# MB_RELAY.net
KiCad netlist of a schematic drawn in Altium Designer
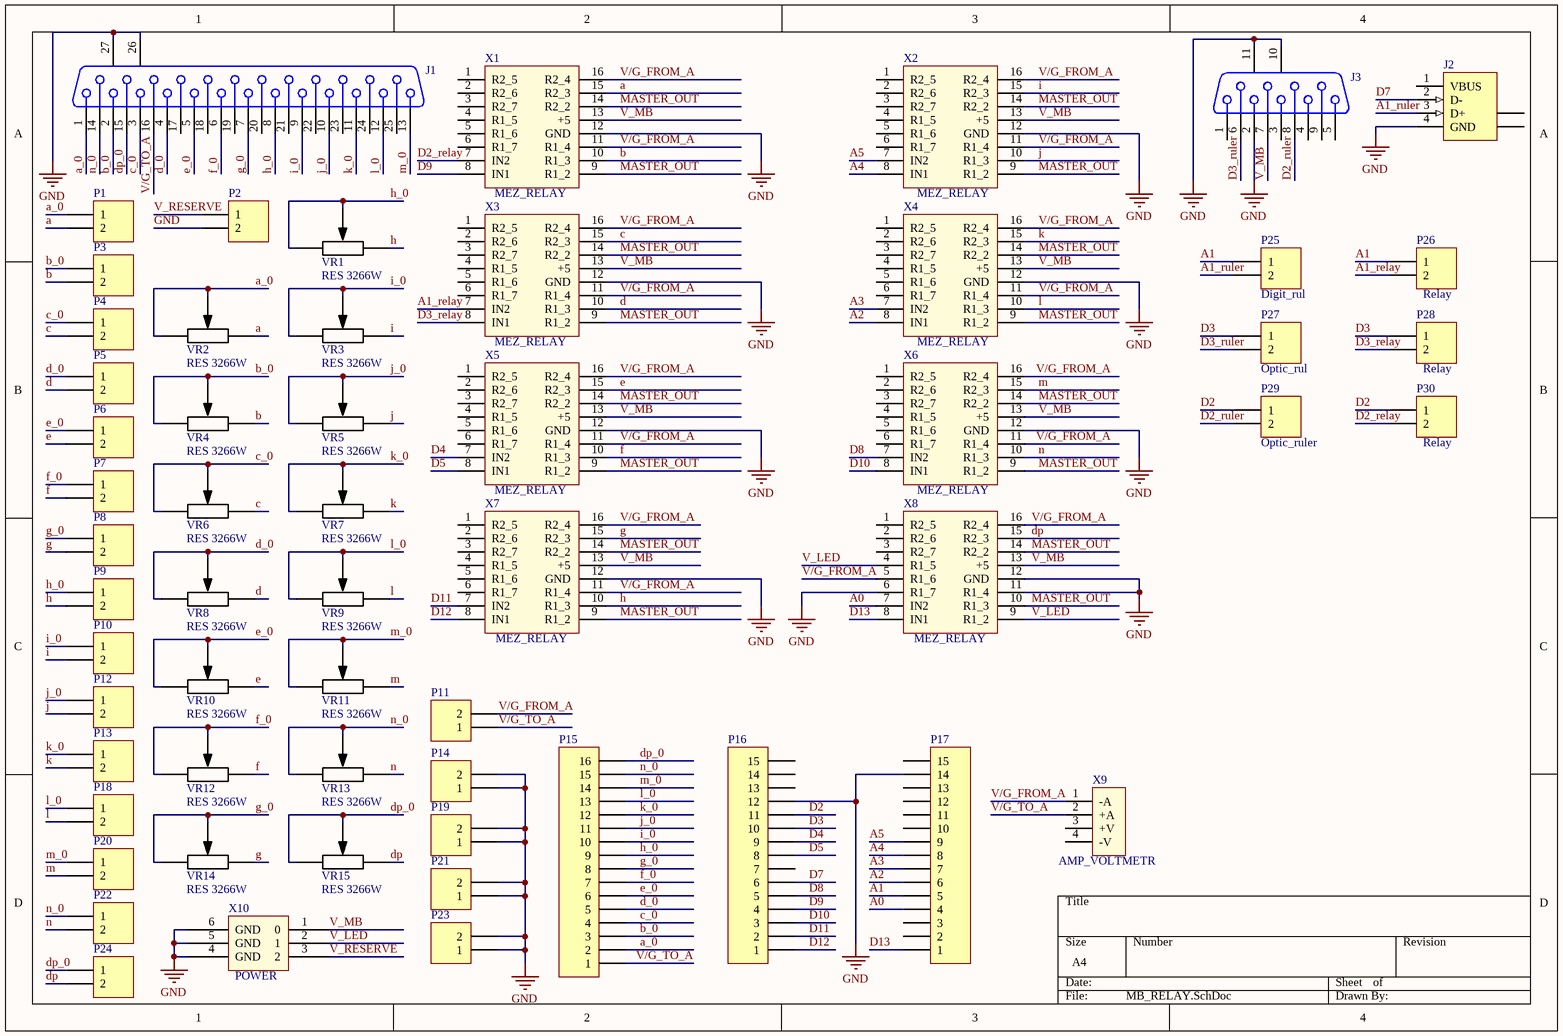
[diagram p0: MB_RELAY.SchDoc]

(export (version "E")
  (design (tool "Eeschema 10.0.6"))
  (components
    (comp (ref "J1")
      (value "D Connector 25")
      (footprint "DSUB1.385-2H25A")
      (description "Receptacle Assembly, 25 Position, Right Angle")
      (fields (field (name "PUBLISHER") "Altium Limited"))
      (libsource (lib "Miscellaneous Connectors") (part "D Connector 25"))
    )
    (comp (ref "J2")
      (value "1-353576-1")
      (footprint "353576")
      (description "USB 1.1, Right Angle, SMT, A Type, Receptacle, 4 Position, White")
      (fields (field (name "PUBLISHER") "Altium Limited"))
      (libsource (lib "AMP Serial Bus USB") (part "1-353576-1"))
    )
    (comp (ref "J3")
      (value "D Connector 9")
      (footprint "DSUB1.385-2H9")
      (description "Receptacle Assembly, 9 Position, Right Angle")
      (fields (field (name "PUBLISHER") "Altium Limited"))
      (libsource (lib "Miscellaneous Connectors") (part "D Connector 9"))
    )
    (comp (ref "P1")
      (value "Header 2")
      (footprint "HDR1X2")
      (description "Header, 2-Pin")
      (fields (field (name "PUBLISHER") "Altium Limited"))
      (libsource (lib "Miscellaneous Connectors") (part "Header 2"))
    )
    (comp (ref "P2")
      (value "Header 2")
      (footprint "HDR1X2")
      (description "Header, 2-Pin")
      (fields (field (name "PUBLISHER") "Altium Limited"))
      (libsource (lib "Miscellaneous Connectors") (part "Header 2"))
    )
    (comp (ref "P3")
      (value "Header 2")
      (footprint "HDR1X2")
      (description "Header, 2-Pin")
      (fields (field (name "PUBLISHER") "Altium Limited"))
      (libsource (lib "Miscellaneous Connectors") (part "Header 2"))
    )
    (comp (ref "P4")
      (value "Header 2")
      (footprint "HDR1X2")
      (description "Header, 2-Pin")
      (fields (field (name "PUBLISHER") "Altium Limited"))
      (libsource (lib "Miscellaneous Connectors") (part "Header 2"))
    )
    (comp (ref "P5")
      (value "Header 2")
      (footprint "HDR1X2")
      (description "Header, 2-Pin")
      (fields (field (name "PUBLISHER") "Altium Limited"))
      (libsource (lib "Miscellaneous Connectors") (part "Header 2"))
    )
    (comp (ref "P6")
      (value "GND")
      (footprint "HDR1X2")
      (description "Header, 2-Pin")
      (fields (field (name "PUBLISHER") "Altium Limited"))
      (libsource (lib "Miscellaneous Connectors") (part "Header 2"))
    )
    (comp (ref "P7")
      (value "GND")
      (footprint "HDR1X2")
      (description "Header, 2-Pin")
      (fields (field (name "PUBLISHER") "Altium Limited"))
      (libsource (lib "Miscellaneous Connectors") (part "Header 2"))
    )
    (comp (ref "P8")
      (value "GND")
      (footprint "HDR1X2")
      (description "Header, 2-Pin")
      (fields (field (name "PUBLISHER") "Altium Limited"))
      (libsource (lib "Miscellaneous Connectors") (part "Header 2"))
    )
    (comp (ref "P9")
      (value "GND")
      (footprint "HDR1X2")
      (description "Header, 2-Pin")
      (fields (field (name "PUBLISHER") "Altium Limited"))
      (libsource (lib "Miscellaneous Connectors") (part "Header 2"))
    )
    (comp (ref "P10")
      (value "Header 2")
      (footprint "HDR1X2")
      (description "Header, 2-Pin")
      (fields (field (name "PUBLISHER") "Altium Limited"))
      (libsource (lib "Miscellaneous Connectors") (part "Header 2"))
    )
    (comp (ref "P11")
      (value "Header 2")
      (footprint "HDR1X2")
      (description "Header, 2-Pin")
      (fields (field (name "PUBLISHER") "Altium Limited"))
      (libsource (lib "") (part "Header 2_1"))
    )
    (comp (ref "P12")
      (value "Header 2")
      (footprint "HDR1X2")
      (description "Header, 2-Pin")
      (fields (field (name "PUBLISHER") "Altium Limited"))
      (libsource (lib "Miscellaneous Connectors") (part "Header 2"))
    )
    (comp (ref "P13")
      (value "GND")
      (footprint "HDR1X2")
      (description "Header, 2-Pin")
      (fields (field (name "PUBLISHER") "Altium Limited"))
      (libsource (lib "Miscellaneous Connectors") (part "Header 2"))
    )
    (comp (ref "P14")
      (value "GND")
      (footprint "HDR1X2")
      (description "Header, 2-Pin")
      (fields (field (name "PUBLISHER") "Altium Limited"))
      (libsource (lib "") (part "Header 2_1"))
    )
    (comp (ref "P15")
      (value "Header 16")
      (footprint "HDR1X16")
      (description "Header, 16-Pin")
      (fields (field (name "PUBLISHER") "Altium Limited"))
      (libsource (lib "Miscellaneous Connectors") (part "Header 16"))
    )
    (comp (ref "P16")
      (value "Header 15")
      (footprint "HDR1X15")
      (description "Header, 15-Pin")
      (fields (field (name "PUBLISHER") "Altium Limited"))
      (libsource (lib "Miscellaneous Connectors") (part "Header 15"))
    )
    (comp (ref "P17")
      (value "Header 15")
      (footprint "HDR1X15")
      (description "Header, 15-Pin")
      (fields (field (name "PUBLISHER") "Altium Limited"))
      (libsource (lib "") (part "Header 15_1"))
    )
    (comp (ref "P18")
      (value "GND")
      (footprint "HDR1X2")
      (description "Header, 2-Pin")
      (fields (field (name "PUBLISHER") "Altium Limited"))
      (libsource (lib "Miscellaneous Connectors") (part "Header 2"))
    )
    (comp (ref "P19")
      (value "GND")
      (footprint "HDR1X2")
      (description "Header, 2-Pin")
      (fields (field (name "PUBLISHER") "Altium Limited"))
      (libsource (lib "") (part "Header 2_1"))
    )
    (comp (ref "P20")
      (value "GND")
      (footprint "HDR1X2")
      (description "Header, 2-Pin")
      (fields (field (name "PUBLISHER") "Altium Limited"))
      (libsource (lib "Miscellaneous Connectors") (part "Header 2"))
    )
    (comp (ref "P21")
      (value "GND")
      (footprint "HDR1X2")
      (description "Header, 2-Pin")
      (fields (field (name "PUBLISHER") "Altium Limited"))
      (libsource (lib "") (part "Header 2_1"))
    )
    (comp (ref "P22")
      (value "GND")
      (footprint "HDR1X2")
      (description "Header, 2-Pin")
      (fields (field (name "PUBLISHER") "Altium Limited"))
      (libsource (lib "Miscellaneous Connectors") (part "Header 2"))
    )
    (comp (ref "P23")
      (value "GND")
      (footprint "HDR1X2")
      (description "Header, 2-Pin")
      (fields (field (name "PUBLISHER") "Altium Limited"))
      (libsource (lib "") (part "Header 2_1"))
    )
    (comp (ref "P24")
      (value "GND")
      (footprint "HDR1X2")
      (description "Header, 2-Pin")
      (fields (field (name "PUBLISHER") "Altium Limited"))
      (libsource (lib "Miscellaneous Connectors") (part "Header 2"))
    )
    (comp (ref "P25")
      (value "Digit_rul")
      (footprint "HDR1X2")
      (description "Header, 2-Pin")
      (fields (field (name "PUBLISHER") "Altium Limited"))
      (libsource (lib "Miscellaneous Connectors") (part "Header 2"))
    )
    (comp (ref "P26")
      (value "Relay")
      (footprint "HDR1X2")
      (description "Header, 2-Pin")
      (fields (field (name "PUBLISHER") "Altium Limited"))
      (libsource (lib "Miscellaneous Connectors") (part "Header 2"))
    )
    (comp (ref "P27")
      (value "Optic_rul")
      (footprint "HDR1X2")
      (description "Header, 2-Pin")
      (fields (field (name "PUBLISHER") "Altium Limited"))
      (libsource (lib "Miscellaneous Connectors") (part "Header 2"))
    )
    (comp (ref "P28")
      (value "Relay")
      (footprint "HDR1X2")
      (description "Header, 2-Pin")
      (fields (field (name "PUBLISHER") "Altium Limited"))
      (libsource (lib "Miscellaneous Connectors") (part "Header 2"))
    )
    (comp (ref "P29")
      (value "Optic_ruler")
      (footprint "HDR1X2")
      (description "Header, 2-Pin")
      (fields (field (name "PUBLISHER") "Altium Limited"))
      (libsource (lib "Miscellaneous Connectors") (part "Header 2"))
    )
    (comp (ref "P30")
      (value "Relay")
      (footprint "HDR1X2")
      (description "Header, 2-Pin")
      (fields (field (name "PUBLISHER") "Altium Limited"))
      (libsource (lib "Miscellaneous Connectors") (part "Header 2"))
    )
    (comp (ref "VR1")
      (value "RES 3266W")
      (footprint "aab_Passive:RES 3266W")
      (libsource (lib "aab_Schlib") (part "RES 3266W"))
    )
    (comp (ref "VR2")
      (value "RES 3266W")
      (footprint "aab_Passive:RES 3266W")
      (libsource (lib "aab_Schlib") (part "RES 3266W"))
    )
    (comp (ref "VR3")
      (value "RES 3266W")
      (footprint "aab_Passive:RES 3266W")
      (libsource (lib "aab_Schlib") (part "RES 3266W"))
    )
    (comp (ref "VR4")
      (value "RES 3266W")
      (footprint "aab_Passive:RES 3266W")
      (libsource (lib "aab_Schlib") (part "RES 3266W"))
    )
    (comp (ref "VR5")
      (value "RES 3266W")
      (footprint "aab_Passive:RES 3266W")
      (libsource (lib "aab_Schlib") (part "RES 3266W"))
    )
    (comp (ref "VR6")
      (value "RES 3266W")
      (footprint "aab_Passive:RES 3266W")
      (libsource (lib "aab_Schlib") (part "RES 3266W"))
    )
    (comp (ref "VR7")
      (value "RES 3266W")
      (footprint "aab_Passive:RES 3266W")
      (libsource (lib "aab_Schlib") (part "RES 3266W"))
    )
    (comp (ref "VR8")
      (value "RES 3266W")
      (footprint "aab_Passive:RES 3266W")
      (libsource (lib "aab_Schlib") (part "RES 3266W"))
    )
    (comp (ref "VR9")
      (value "RES 3266W")
      (footprint "aab_Passive:RES 3266W")
      (libsource (lib "aab_Schlib") (part "RES 3266W"))
    )
    (comp (ref "VR10")
      (value "RES 3266W")
      (footprint "aab_Passive:RES 3266W")
      (libsource (lib "aab_Schlib") (part "RES 3266W"))
    )
    (comp (ref "VR11")
      (value "RES 3266W")
      (footprint "aab_Passive:RES 3266W")
      (libsource (lib "aab_Schlib") (part "RES 3266W"))
    )
    (comp (ref "VR12")
      (value "RES 3266W")
      (footprint "aab_Passive:RES 3266W")
      (libsource (lib "aab_Schlib") (part "RES 3266W"))
    )
    (comp (ref "VR13")
      (value "RES 3266W")
      (footprint "aab_Passive:RES 3266W")
      (libsource (lib "aab_Schlib") (part "RES 3266W"))
    )
    (comp (ref "VR14")
      (value "RES 3266W")
      (footprint "aab_Passive:RES 3266W")
      (libsource (lib "aab_Schlib") (part "RES 3266W"))
    )
    (comp (ref "VR15")
      (value "RES 3266W")
      (footprint "aab_Passive:RES 3266W")
      (libsource (lib "aab_Schlib") (part "RES 3266W"))
    )
    (comp (ref "X1")
      (value "MEZ_RELAY")
      (footprint "MEZ_RELAY")
      (libsource (lib "msp_SchLib") (part "MEZ_RELAY"))
    )
    (comp (ref "X2")
      (value "MEZ_RELAY")
      (footprint "MEZ_RELAY")
      (libsource (lib "msp_SchLib") (part "MEZ_RELAY"))
    )
    (comp (ref "X3")
      (value "MEZ_RELAY")
      (footprint "MEZ_RELAY")
      (libsource (lib "msp_SchLib") (part "MEZ_RELAY"))
    )
    (comp (ref "X4")
      (value "MEZ_RELAY")
      (footprint "MEZ_RELAY")
      (libsource (lib "msp_SchLib") (part "MEZ_RELAY"))
    )
    (comp (ref "X5")
      (value "MEZ_RELAY")
      (footprint "MEZ_RELAY")
      (libsource (lib "msp_SchLib") (part "MEZ_RELAY"))
    )
    (comp (ref "X6")
      (value "MEZ_RELAY")
      (footprint "MEZ_RELAY")
      (libsource (lib "msp_SchLib") (part "MEZ_RELAY"))
    )
    (comp (ref "X7")
      (value "MEZ_RELAY")
      (footprint "MEZ_RELAY")
      (libsource (lib "msp_SchLib") (part "MEZ_RELAY"))
    )
    (comp (ref "X8")
      (value "MEZ_RELAY")
      (footprint "MEZ_RELAY")
      (libsource (lib "msp_SchLib") (part "MEZ_RELAY"))
    )
    (comp (ref "X9")
      (value "AMP_VOLTMETR")
      (footprint "vpl_Passive:AMP_VOLTMETER")
      (libsource (lib "msp_SchLib") (part "AMP_VOLTMETR"))
    )
    (comp (ref "X10")
      (value "POWER")
      (footprint "vpl_Passive:POWER")
      (libsource (lib "msp_SchLib") (part "POWER"))
    )
  )
  (nets
    (net (code "1") (name "/A0") (class "Default")
      (node (ref "P17") (pin "4") (pinfunction "4_4") (pintype "passive"))
      (node (ref "X8") (pin "7") (pinfunction "IN2_7") (pintype "passive"))
    )
    (net (code "2") (name "/A1") (class "Default")
      (node (ref "P17") (pin "5") (pinfunction "5_5") (pintype "passive"))
      (node (ref "P25") (pin "1") (pinfunction "1_1") (pintype "passive"))
      (node (ref "P26") (pin "1") (pinfunction "1_1") (pintype "passive"))
    )
    (net (code "3") (name "/A1_relay") (class "Default")
      (node (ref "P26") (pin "2") (pinfunction "2_2") (pintype "passive"))
      (node (ref "X3") (pin "7") (pinfunction "IN2_7") (pintype "passive"))
    )
    (net (code "4") (name "/A1_ruler") (class "Default")
      (node (ref "J2") (pin "3") (pinfunction "D+_3") (pintype "input"))
      (node (ref "P25") (pin "2") (pinfunction "2_2") (pintype "passive"))
    )
    (net (code "5") (name "/A2") (class "Default")
      (node (ref "P17") (pin "6") (pinfunction "6_6") (pintype "passive"))
      (node (ref "X4") (pin "8") (pinfunction "IN1_8") (pintype "passive"))
    )
    (net (code "6") (name "/A3") (class "Default")
      (node (ref "P17") (pin "7") (pinfunction "7_7") (pintype "passive"))
      (node (ref "X4") (pin "7") (pinfunction "IN2_7") (pintype "passive"))
    )
    (net (code "7") (name "/A4") (class "Default")
      (node (ref "P17") (pin "8") (pinfunction "8_8") (pintype "passive"))
      (node (ref "X2") (pin "8") (pinfunction "IN1_8") (pintype "passive"))
    )
    (net (code "8") (name "/A5") (class "Default")
      (node (ref "P17") (pin "9") (pinfunction "9_9") (pintype "passive"))
      (node (ref "X2") (pin "7") (pinfunction "IN2_7") (pintype "passive"))
    )
    (net (code "9") (name "/D2") (class "Default")
      (node (ref "P16") (pin "11") (pinfunction "11_11") (pintype "passive"))
      (node (ref "P29") (pin "1") (pinfunction "1_1") (pintype "passive"))
      (node (ref "P30") (pin "1") (pinfunction "1_1") (pintype "passive"))
    )
    (net (code "10") (name "/D2_relay") (class "Default")
      (node (ref "P30") (pin "2") (pinfunction "2_2") (pintype "passive"))
      (node (ref "X1") (pin "7") (pinfunction "IN2_7") (pintype "passive"))
    )
    (net (code "11") (name "/D2_ruler") (class "Default")
      (node (ref "J3") (pin "8") (pinfunction "8_8") (pintype "passive"))
      (node (ref "P29") (pin "2") (pinfunction "2_2") (pintype "passive"))
    )
    (net (code "12") (name "/D3") (class "Default")
      (node (ref "P16") (pin "10") (pinfunction "10_10") (pintype "passive"))
      (node (ref "P27") (pin "1") (pinfunction "1_1") (pintype "passive"))
      (node (ref "P28") (pin "1") (pinfunction "1_1") (pintype "passive"))
    )
    (net (code "13") (name "/D3_relay") (class "Default")
      (node (ref "P28") (pin "2") (pinfunction "2_2") (pintype "passive"))
      (node (ref "X3") (pin "8") (pinfunction "IN1_8") (pintype "passive"))
    )
    (net (code "14") (name "/D3_ruler") (class "Default")
      (node (ref "J3") (pin "6") (pinfunction "6_6") (pintype "passive"))
      (node (ref "P27") (pin "2") (pinfunction "2_2") (pintype "passive"))
    )
    (net (code "15") (name "/D4") (class "Default")
      (node (ref "P16") (pin "9") (pinfunction "9_9") (pintype "passive"))
      (node (ref "X5") (pin "7") (pinfunction "IN2_7") (pintype "passive"))
    )
    (net (code "16") (name "/D5") (class "Default")
      (node (ref "P16") (pin "8") (pinfunction "8_8") (pintype "passive"))
      (node (ref "X5") (pin "8") (pinfunction "IN1_8") (pintype "passive"))
    )
    (net (code "17") (name "/D7") (class "Default")
      (node (ref "J2") (pin "2") (pinfunction "D-_2") (pintype "input"))
      (node (ref "P16") (pin "6") (pinfunction "6_6") (pintype "passive"))
    )
    (net (code "18") (name "/D8") (class "Default")
      (node (ref "P16") (pin "5") (pinfunction "5_5") (pintype "passive"))
      (node (ref "X6") (pin "7") (pinfunction "IN2_7") (pintype "passive"))
    )
    (net (code "19") (name "/D9") (class "Default")
      (node (ref "P16") (pin "4") (pinfunction "4_4") (pintype "passive"))
      (node (ref "X1") (pin "8") (pinfunction "IN1_8") (pintype "passive"))
    )
    (net (code "20") (name "/D10") (class "Default")
      (node (ref "P16") (pin "3") (pinfunction "3_3") (pintype "passive"))
      (node (ref "X6") (pin "8") (pinfunction "IN1_8") (pintype "passive"))
    )
    (net (code "21") (name "/D11") (class "Default")
      (node (ref "P16") (pin "2") (pinfunction "2_2") (pintype "passive"))
      (node (ref "X7") (pin "7") (pinfunction "IN2_7") (pintype "passive"))
    )
    (net (code "22") (name "/D12") (class "Default")
      (node (ref "P16") (pin "1") (pinfunction "1_1") (pintype "passive"))
      (node (ref "X7") (pin "8") (pinfunction "IN1_8") (pintype "passive"))
    )
    (net (code "23") (name "/D13") (class "Default")
      (node (ref "P17") (pin "1") (pinfunction "1_1") (pintype "passive"))
      (node (ref "X8") (pin "8") (pinfunction "IN1_8") (pintype "passive"))
    )
    (net (code "24") (name "/MASTER_OUT") (class "Default")
      (node (ref "X1") (pin "14") (pinfunction "R2_2_14") (pintype "passive"))
      (node (ref "X1") (pin "9") (pinfunction "R1_2_9") (pintype "passive"))
      (node (ref "X2") (pin "14") (pinfunction "R2_2_14") (pintype "passive"))
      (node (ref "X2") (pin "9") (pinfunction "R1_2_9") (pintype "passive"))
      (node (ref "X3") (pin "14") (pinfunction "R2_2_14") (pintype "passive"))
      (node (ref "X3") (pin "9") (pinfunction "R1_2_9") (pintype "passive"))
      (node (ref "X4") (pin "14") (pinfunction "R2_2_14") (pintype "passive"))
      (node (ref "X4") (pin "9") (pinfunction "R1_2_9") (pintype "passive"))
      (node (ref "X5") (pin "14") (pinfunction "R2_2_14") (pintype "passive"))
      (node (ref "X5") (pin "9") (pinfunction "R1_2_9") (pintype "passive"))
      (node (ref "X6") (pin "14") (pinfunction "R2_2_14") (pintype "passive"))
      (node (ref "X6") (pin "9") (pinfunction "R1_2_9") (pintype "passive"))
      (node (ref "X7") (pin "14") (pinfunction "R2_2_14") (pintype "passive"))
      (node (ref "X7") (pin "9") (pinfunction "R1_2_9") (pintype "passive"))
      (node (ref "X8") (pin "10") (pinfunction "R1_3_10") (pintype "passive"))
      (node (ref "X8") (pin "14") (pinfunction "R2_2_14") (pintype "passive"))
    )
    (net (code "25") (name "/V_LED") (class "Default")
      (node (ref "X10") (pin "2") (pinfunction "1_2") (pintype "passive"))
      (node (ref "X8") (pin "4") (pinfunction "R1_5_4") (pintype "passive"))
      (node (ref "X8") (pin "9") (pinfunction "R1_2_9") (pintype "passive"))
    )
    (net (code "26") (name "/V_MB") (class "Default")
      (node (ref "J3") (pin "7") (pinfunction "7_7") (pintype "passive"))
      (node (ref "X1") (pin "13") (pinfunction "+5_13") (pintype "passive"))
      (node (ref "X10") (pin "1") (pinfunction "0_1") (pintype "passive"))
      (node (ref "X2") (pin "13") (pinfunction "+5_13") (pintype "passive"))
      (node (ref "X3") (pin "13") (pinfunction "+5_13") (pintype "passive"))
      (node (ref "X4") (pin "13") (pinfunction "+5_13") (pintype "passive"))
      (node (ref "X5") (pin "13") (pinfunction "+5_13") (pintype "passive"))
      (node (ref "X6") (pin "13") (pinfunction "+5_13") (pintype "passive"))
      (node (ref "X7") (pin "13") (pinfunction "+5_13") (pintype "passive"))
      (node (ref "X8") (pin "13") (pinfunction "+5_13") (pintype "passive"))
    )
    (net (code "27") (name "/V_RESERVE") (class "Default")
      (node (ref "P2") (pin "1") (pinfunction "1_1") (pintype "passive"))
      (node (ref "X10") (pin "3") (pinfunction "2_3") (pintype "passive"))
    )
    (net (code "28") (name "/V{slash}G_FROM_A") (class "Default")
      (node (ref "P11") (pin "2") (pinfunction "2_2") (pintype "passive"))
      (node (ref "X1") (pin "11") (pinfunction "R1_4_11") (pintype "passive"))
      (node (ref "X1") (pin "16") (pinfunction "R2_4_16") (pintype "passive"))
      (node (ref "X2") (pin "11") (pinfunction "R1_4_11") (pintype "passive"))
      (node (ref "X2") (pin "16") (pinfunction "R2_4_16") (pintype "passive"))
      (node (ref "X3") (pin "11") (pinfunction "R1_4_11") (pintype "passive"))
      (node (ref "X3") (pin "16") (pinfunction "R2_4_16") (pintype "passive"))
      (node (ref "X4") (pin "11") (pinfunction "R1_4_11") (pintype "passive"))
      (node (ref "X4") (pin "16") (pinfunction "R2_4_16") (pintype "passive"))
      (node (ref "X5") (pin "11") (pinfunction "R1_4_11") (pintype "passive"))
      (node (ref "X5") (pin "16") (pinfunction "R2_4_16") (pintype "passive"))
      (node (ref "X6") (pin "11") (pinfunction "R1_4_11") (pintype "passive"))
      (node (ref "X6") (pin "16") (pinfunction "R2_4_16") (pintype "passive"))
      (node (ref "X7") (pin "11") (pinfunction "R1_4_11") (pintype "passive"))
      (node (ref "X7") (pin "16") (pinfunction "R2_4_16") (pintype "passive"))
      (node (ref "X8") (pin "16") (pinfunction "R2_4_16") (pintype "passive"))
      (node (ref "X8") (pin "5") (pinfunction "R1_6_5") (pintype "passive"))
      (node (ref "X9") (pin "1") (pinfunction "-A_1") (pintype "passive"))
    )
    (net (code "29") (name "/V{slash}G_TO_A") (class "Default")
      (node (ref "J1") (pin "16") (pinfunction "16_16") (pintype "passive"))
      (node (ref "P11") (pin "1") (pinfunction "1_1") (pintype "passive"))
      (node (ref "P15") (pin "1") (pinfunction "1_1") (pintype "passive"))
      (node (ref "X9") (pin "2") (pinfunction "+A_2") (pintype "passive"))
    )
    (net (code "30") (name "/a") (class "Default")
      (node (ref "P1") (pin "2") (pinfunction "2_2") (pintype "passive"))
      (node (ref "VR2") (pin "3") (pinfunction "3_3") (pintype "passive"))
      (node (ref "X1") (pin "15") (pinfunction "R2_3_15") (pintype "passive"))
    )
    (net (code "31") (name "/a_0") (class "Default")
      (node (ref "J1") (pin "1") (pinfunction "1_1") (pintype "passive"))
      (node (ref "P1") (pin "1") (pinfunction "1_1") (pintype "passive"))
      (node (ref "P15") (pin "2") (pinfunction "2_2") (pintype "passive"))
      (node (ref "VR2") (pin "1") (pinfunction "1_1") (pintype "passive"))
      (node (ref "VR2") (pin "2") (pinfunction "2_2") (pintype "passive"))
    )
    (net (code "32") (name "/b") (class "Default")
      (node (ref "P3") (pin "2") (pinfunction "2_2") (pintype "passive"))
      (node (ref "VR4") (pin "3") (pinfunction "3_3") (pintype "passive"))
      (node (ref "X1") (pin "10") (pinfunction "R1_3_10") (pintype "passive"))
    )
    (net (code "33") (name "/b_0") (class "Default")
      (node (ref "J1") (pin "2") (pinfunction "2_2") (pintype "passive"))
      (node (ref "P15") (pin "3") (pinfunction "3_3") (pintype "passive"))
      (node (ref "P3") (pin "1") (pinfunction "1_1") (pintype "passive"))
      (node (ref "VR4") (pin "1") (pinfunction "1_1") (pintype "passive"))
      (node (ref "VR4") (pin "2") (pinfunction "2_2") (pintype "passive"))
    )
    (net (code "34") (name "/c") (class "Default")
      (node (ref "P4") (pin "2") (pinfunction "2_2") (pintype "passive"))
      (node (ref "VR6") (pin "3") (pinfunction "3_3") (pintype "passive"))
      (node (ref "X3") (pin "15") (pinfunction "R2_3_15") (pintype "passive"))
    )
    (net (code "35") (name "/c_0") (class "Default")
      (node (ref "J1") (pin "3") (pinfunction "3_3") (pintype "passive"))
      (node (ref "P15") (pin "4") (pinfunction "4_4") (pintype "passive"))
      (node (ref "P4") (pin "1") (pinfunction "1_1") (pintype "passive"))
      (node (ref "VR6") (pin "1") (pinfunction "1_1") (pintype "passive"))
      (node (ref "VR6") (pin "2") (pinfunction "2_2") (pintype "passive"))
    )
    (net (code "36") (name "/d") (class "Default")
      (node (ref "P5") (pin "2") (pinfunction "2_2") (pintype "passive"))
      (node (ref "VR8") (pin "3") (pinfunction "3_3") (pintype "passive"))
      (node (ref "X3") (pin "10") (pinfunction "R1_3_10") (pintype "passive"))
    )
    (net (code "37") (name "/d_0") (class "Default")
      (node (ref "J1") (pin "4") (pinfunction "4_4") (pintype "passive"))
      (node (ref "P15") (pin "5") (pinfunction "5_5") (pintype "passive"))
      (node (ref "P5") (pin "1") (pinfunction "1_1") (pintype "passive"))
      (node (ref "VR8") (pin "1") (pinfunction "1_1") (pintype "passive"))
      (node (ref "VR8") (pin "2") (pinfunction "2_2") (pintype "passive"))
    )
    (net (code "38") (name "/dp") (class "Default")
      (node (ref "P24") (pin "2") (pinfunction "2_2") (pintype "passive"))
      (node (ref "VR15") (pin "3") (pinfunction "3_3") (pintype "passive"))
      (node (ref "X8") (pin "15") (pinfunction "R2_3_15") (pintype "passive"))
    )
    (net (code "39") (name "/dp_0") (class "Default")
      (node (ref "J1") (pin "15") (pinfunction "15_15") (pintype "passive"))
      (node (ref "P15") (pin "16") (pinfunction "16_16") (pintype "passive"))
      (node (ref "P24") (pin "1") (pinfunction "1_1") (pintype "passive"))
      (node (ref "VR15") (pin "1") (pinfunction "1_1") (pintype "passive"))
      (node (ref "VR15") (pin "2") (pinfunction "2_2") (pintype "passive"))
    )
    (net (code "40") (name "/e") (class "Default")
      (node (ref "P6") (pin "2") (pinfunction "2_2") (pintype "passive"))
      (node (ref "VR10") (pin "3") (pinfunction "3_3") (pintype "passive"))
      (node (ref "X5") (pin "15") (pinfunction "R2_3_15") (pintype "passive"))
    )
    (net (code "41") (name "/e_0") (class "Default")
      (node (ref "J1") (pin "5") (pinfunction "5_5") (pintype "passive"))
      (node (ref "P15") (pin "6") (pinfunction "6_6") (pintype "passive"))
      (node (ref "P6") (pin "1") (pinfunction "1_1") (pintype "passive"))
      (node (ref "VR10") (pin "1") (pinfunction "1_1") (pintype "passive"))
      (node (ref "VR10") (pin "2") (pinfunction "2_2") (pintype "passive"))
    )
    (net (code "42") (name "/f") (class "Default")
      (node (ref "P7") (pin "2") (pinfunction "2_2") (pintype "passive"))
      (node (ref "VR12") (pin "3") (pinfunction "3_3") (pintype "passive"))
      (node (ref "X5") (pin "10") (pinfunction "R1_3_10") (pintype "passive"))
    )
    (net (code "43") (name "/f_0") (class "Default")
      (node (ref "J1") (pin "6") (pinfunction "6_6") (pintype "passive"))
      (node (ref "P15") (pin "7") (pinfunction "7_7") (pintype "passive"))
      (node (ref "P7") (pin "1") (pinfunction "1_1") (pintype "passive"))
      (node (ref "VR12") (pin "1") (pinfunction "1_1") (pintype "passive"))
      (node (ref "VR12") (pin "2") (pinfunction "2_2") (pintype "passive"))
    )
    (net (code "44") (name "/g") (class "Default")
      (node (ref "P8") (pin "2") (pinfunction "2_2") (pintype "passive"))
      (node (ref "VR14") (pin "3") (pinfunction "3_3") (pintype "passive"))
      (node (ref "X7") (pin "15") (pinfunction "R2_3_15") (pintype "passive"))
    )
    (net (code "45") (name "/g_0") (class "Default")
      (node (ref "J1") (pin "7") (pinfunction "7_7") (pintype "passive"))
      (node (ref "P15") (pin "8") (pinfunction "8_8") (pintype "passive"))
      (node (ref "P8") (pin "1") (pinfunction "1_1") (pintype "passive"))
      (node (ref "VR14") (pin "1") (pinfunction "1_1") (pintype "passive"))
      (node (ref "VR14") (pin "2") (pinfunction "2_2") (pintype "passive"))
    )
    (net (code "46") (name "/h") (class "Default")
      (node (ref "P9") (pin "2") (pinfunction "2_2") (pintype "passive"))
      (node (ref "VR1") (pin "3") (pinfunction "3_3") (pintype "passive"))
      (node (ref "X7") (pin "10") (pinfunction "R1_3_10") (pintype "passive"))
    )
    (net (code "47") (name "/h_0") (class "Default")
      (node (ref "J1") (pin "8") (pinfunction "8_8") (pintype "passive"))
      (node (ref "P15") (pin "9") (pinfunction "9_9") (pintype "passive"))
      (node (ref "P9") (pin "1") (pinfunction "1_1") (pintype "passive"))
      (node (ref "VR1") (pin "1") (pinfunction "1_1") (pintype "passive"))
      (node (ref "VR1") (pin "2") (pinfunction "2_2") (pintype "passive"))
    )
    (net (code "48") (name "/i") (class "Default")
      (node (ref "P10") (pin "2") (pinfunction "2_2") (pintype "passive"))
      (node (ref "VR3") (pin "3") (pinfunction "3_3") (pintype "passive"))
      (node (ref "X2") (pin "15") (pinfunction "R2_3_15") (pintype "passive"))
    )
    (net (code "49") (name "/i_0") (class "Default")
      (node (ref "J1") (pin "9") (pinfunction "9_9") (pintype "passive"))
      (node (ref "P10") (pin "1") (pinfunction "1_1") (pintype "passive"))
      (node (ref "P15") (pin "10") (pinfunction "10_10") (pintype "passive"))
      (node (ref "VR3") (pin "1") (pinfunction "1_1") (pintype "passive"))
      (node (ref "VR3") (pin "2") (pinfunction "2_2") (pintype "passive"))
    )
    (net (code "50") (name "/j") (class "Default")
      (node (ref "P12") (pin "2") (pinfunction "2_2") (pintype "passive"))
      (node (ref "VR5") (pin "3") (pinfunction "3_3") (pintype "passive"))
      (node (ref "X2") (pin "10") (pinfunction "R1_3_10") (pintype "passive"))
    )
    (net (code "51") (name "/j_0") (class "Default")
      (node (ref "J1") (pin "10") (pinfunction "10_10") (pintype "passive"))
      (node (ref "P12") (pin "1") (pinfunction "1_1") (pintype "passive"))
      (node (ref "P15") (pin "11") (pinfunction "11_11") (pintype "passive"))
      (node (ref "VR5") (pin "1") (pinfunction "1_1") (pintype "passive"))
      (node (ref "VR5") (pin "2") (pinfunction "2_2") (pintype "passive"))
    )
    (net (code "52") (name "/k") (class "Default")
      (node (ref "P13") (pin "2") (pinfunction "2_2") (pintype "passive"))
      (node (ref "VR7") (pin "3") (pinfunction "3_3") (pintype "passive"))
      (node (ref "X4") (pin "15") (pinfunction "R2_3_15") (pintype "passive"))
    )
    (net (code "53") (name "/k_0") (class "Default")
      (node (ref "J1") (pin "11") (pinfunction "11_11") (pintype "passive"))
      (node (ref "P13") (pin "1") (pinfunction "1_1") (pintype "passive"))
      (node (ref "P15") (pin "12") (pinfunction "12_12") (pintype "passive"))
      (node (ref "VR7") (pin "1") (pinfunction "1_1") (pintype "passive"))
      (node (ref "VR7") (pin "2") (pinfunction "2_2") (pintype "passive"))
    )
    (net (code "54") (name "/l") (class "Default")
      (node (ref "P18") (pin "2") (pinfunction "2_2") (pintype "passive"))
      (node (ref "VR9") (pin "3") (pinfunction "3_3") (pintype "passive"))
      (node (ref "X4") (pin "10") (pinfunction "R1_3_10") (pintype "passive"))
    )
    (net (code "55") (name "/l_0") (class "Default")
      (node (ref "J1") (pin "12") (pinfunction "12_12") (pintype "passive"))
      (node (ref "P15") (pin "13") (pinfunction "13_13") (pintype "passive"))
      (node (ref "P18") (pin "1") (pinfunction "1_1") (pintype "passive"))
      (node (ref "VR9") (pin "1") (pinfunction "1_1") (pintype "passive"))
      (node (ref "VR9") (pin "2") (pinfunction "2_2") (pintype "passive"))
    )
    (net (code "56") (name "/m") (class "Default")
      (node (ref "P20") (pin "2") (pinfunction "2_2") (pintype "passive"))
      (node (ref "VR11") (pin "3") (pinfunction "3_3") (pintype "passive"))
      (node (ref "X6") (pin "15") (pinfunction "R2_3_15") (pintype "passive"))
    )
    (net (code "57") (name "/m_0") (class "Default")
      (node (ref "J1") (pin "13") (pinfunction "13_13") (pintype "passive"))
      (node (ref "P15") (pin "14") (pinfunction "14_14") (pintype "passive"))
      (node (ref "P20") (pin "1") (pinfunction "1_1") (pintype "passive"))
      (node (ref "VR11") (pin "1") (pinfunction "1_1") (pintype "passive"))
      (node (ref "VR11") (pin "2") (pinfunction "2_2") (pintype "passive"))
    )
    (net (code "58") (name "/n") (class "Default")
      (node (ref "P22") (pin "2") (pinfunction "2_2") (pintype "passive"))
      (node (ref "VR13") (pin "3") (pinfunction "3_3") (pintype "passive"))
      (node (ref "X6") (pin "10") (pinfunction "R1_3_10") (pintype "passive"))
    )
    (net (code "59") (name "/n_0") (class "Default")
      (node (ref "J1") (pin "14") (pinfunction "14_14") (pintype "passive"))
      (node (ref "P15") (pin "15") (pinfunction "15_15") (pintype "passive"))
      (node (ref "P22") (pin "1") (pinfunction "1_1") (pintype "passive"))
      (node (ref "VR13") (pin "1") (pinfunction "1_1") (pintype "passive"))
      (node (ref "VR13") (pin "2") (pinfunction "2_2") (pintype "passive"))
    )
    (net (code "60") (name "GND") (class "Default")
      (node (ref "J1") (pin "26") (pinfunction "MH1_26") (pintype "passive"))
      (node (ref "J1") (pin "27") (pinfunction "MH2_27") (pintype "passive"))
      (node (ref "J2") (pin "4") (pinfunction "GND_4") (pintype "power_in"))
      (node (ref "J3") (pin "10") (pinfunction "MH1_10") (pintype "passive"))
      (node (ref "J3") (pin "11") (pinfunction "MH2_11") (pintype "passive"))
      (node (ref "J3") (pin "2") (pinfunction "2_2") (pintype "passive"))
      (node (ref "P14") (pin "1") (pinfunction "1_1") (pintype "passive"))
      (node (ref "P14") (pin "2") (pinfunction "2_2") (pintype "passive"))
      (node (ref "P16") (pin "12") (pinfunction "12_12") (pintype "passive"))
      (node (ref "P17") (pin "14") (pinfunction "14_14") (pintype "passive"))
      (node (ref "P19") (pin "1") (pinfunction "1_1") (pintype "passive"))
      (node (ref "P19") (pin "2") (pinfunction "2_2") (pintype "passive"))
      (node (ref "P2") (pin "2") (pinfunction "2_2") (pintype "passive"))
      (node (ref "P21") (pin "1") (pinfunction "1_1") (pintype "passive"))
      (node (ref "P21") (pin "2") (pinfunction "2_2") (pintype "passive"))
      (node (ref "P23") (pin "1") (pinfunction "1_1") (pintype "passive"))
      (node (ref "P23") (pin "2") (pinfunction "2_2") (pintype "passive"))
      (node (ref "X1") (pin "12") (pinfunction "GND_12") (pintype "passive"))
      (node (ref "X10") (pin "4") (pinfunction "GND_4") (pintype "passive"))
      (node (ref "X10") (pin "5") (pinfunction "GND_5") (pintype "passive"))
      (node (ref "X10") (pin "6") (pinfunction "GND_6") (pintype "passive"))
      (node (ref "X2") (pin "12") (pinfunction "GND_12") (pintype "passive"))
      (node (ref "X3") (pin "12") (pinfunction "GND_12") (pintype "passive"))
      (node (ref "X4") (pin "12") (pinfunction "GND_12") (pintype "passive"))
      (node (ref "X5") (pin "12") (pinfunction "GND_12") (pintype "passive"))
      (node (ref "X6") (pin "12") (pinfunction "GND_12") (pintype "passive"))
      (node (ref "X7") (pin "12") (pinfunction "GND_12") (pintype "passive"))
      (node (ref "X8") (pin "11") (pinfunction "R1_4_11") (pintype "passive"))
      (node (ref "X8") (pin "12") (pinfunction "GND_12") (pintype "passive"))
      (node (ref "X8") (pin "6") (pinfunction "R1_7_6") (pintype "passive"))
    )
    (net (code "61") (name "unconnected-(J1-Pad17)") (class "Default")
      (node (ref "J1") (pin "17") (pinfunction "17_17") (pintype "passive"))
    )
    (net (code "62") (name "unconnected-(J1-Pad18)") (class "Default")
      (node (ref "J1") (pin "18") (pinfunction "18_18") (pintype "passive"))
    )
    (net (code "63") (name "unconnected-(J1-Pad19)") (class "Default")
      (node (ref "J1") (pin "19") (pinfunction "19_19") (pintype "passive"))
    )
    (net (code "64") (name "unconnected-(J1-Pad20)") (class "Default")
      (node (ref "J1") (pin "20") (pinfunction "20_20") (pintype "passive"))
    )
    (net (code "65") (name "unconnected-(J1-Pad21)") (class "Default")
      (node (ref "J1") (pin "21") (pinfunction "21_21") (pintype "passive"))
    )
    (net (code "66") (name "unconnected-(J1-Pad22)") (class "Default")
      (node (ref "J1") (pin "22") (pinfunction "22_22") (pintype "passive"))
    )
    (net (code "67") (name "unconnected-(J1-Pad23)") (class "Default")
      (node (ref "J1") (pin "23") (pinfunction "23_23") (pintype "passive"))
    )
    (net (code "68") (name "unconnected-(J1-Pad24)") (class "Default")
      (node (ref "J1") (pin "24") (pinfunction "24_24") (pintype "passive"))
    )
    (net (code "69") (name "unconnected-(J1-Pad25)") (class "Default")
      (node (ref "J1") (pin "25") (pinfunction "25_25") (pintype "passive"))
    )
    (net (code "70") (name "unconnected-(J2-SHLD-Pad5)") (class "Default")
      (node (ref "J2") (pin "5") (pinfunction "SHLD_5") (pintype "passive"))
    )
    (net (code "71") (name "unconnected-(J2-SHLD-Pad6)") (class "Default")
      (node (ref "J2") (pin "6") (pinfunction "SHLD_6") (pintype "passive"))
    )
    (net (code "72") (name "unconnected-(J2-VBUS-Pad1)") (class "Default")
      (node (ref "J2") (pin "1") (pinfunction "VBUS_1") (pintype "power_in"))
    )
    (net (code "73") (name "unconnected-(J3-Pad1)") (class "Default")
      (node (ref "J3") (pin "1") (pinfunction "1_1") (pintype "passive"))
    )
    (net (code "74") (name "unconnected-(J3-Pad3)") (class "Default")
      (node (ref "J3") (pin "3") (pinfunction "3_3") (pintype "passive"))
    )
    (net (code "75") (name "unconnected-(J3-Pad4)") (class "Default")
      (node (ref "J3") (pin "4") (pinfunction "4_4") (pintype "passive"))
    )
    (net (code "76") (name "unconnected-(J3-Pad5)") (class "Default")
      (node (ref "J3") (pin "5") (pinfunction "5_5") (pintype "passive"))
    )
    (net (code "77") (name "unconnected-(J3-Pad9)") (class "Default")
      (node (ref "J3") (pin "9") (pinfunction "9_9") (pintype "passive"))
    )
    (net (code "78") (name "unconnected-(P16-Pad7)") (class "Default")
      (node (ref "P16") (pin "7") (pinfunction "7_7") (pintype "passive"))
    )
    (net (code "79") (name "unconnected-(P16-Pad13)") (class "Default")
      (node (ref "P16") (pin "13") (pinfunction "13_13") (pintype "passive"))
    )
    (net (code "80") (name "unconnected-(P16-Pad14)") (class "Default")
      (node (ref "P16") (pin "14") (pinfunction "14_14") (pintype "passive"))
    )
    (net (code "81") (name "unconnected-(P16-Pad15)") (class "Default")
      (node (ref "P16") (pin "15") (pinfunction "15_15") (pintype "passive"))
    )
    (net (code "82") (name "unconnected-(P17-Pad2)") (class "Default")
      (node (ref "P17") (pin "2") (pinfunction "2_2") (pintype "passive"))
    )
    (net (code "83") (name "unconnected-(P17-Pad3)") (class "Default")
      (node (ref "P17") (pin "3") (pinfunction "3_3") (pintype "passive"))
    )
    (net (code "84") (name "unconnected-(P17-Pad10)") (class "Default")
      (node (ref "P17") (pin "10") (pinfunction "10_10") (pintype "passive"))
    )
    (net (code "85") (name "unconnected-(P17-Pad11)") (class "Default")
      (node (ref "P17") (pin "11") (pinfunction "11_11") (pintype "passive"))
    )
    (net (code "86") (name "unconnected-(P17-Pad12)") (class "Default")
      (node (ref "P17") (pin "12") (pinfunction "12_12") (pintype "passive"))
    )
    (net (code "87") (name "unconnected-(P17-Pad13)") (class "Default")
      (node (ref "P17") (pin "13") (pinfunction "13_13") (pintype "passive"))
    )
    (net (code "88") (name "unconnected-(P17-Pad15)") (class "Default")
      (node (ref "P17") (pin "15") (pinfunction "15_15") (pintype "passive"))
    )
    (net (code "89") (name "unconnected-(X1-R1_5-Pad4)") (class "Default")
      (node (ref "X1") (pin "4") (pinfunction "R1_5_4") (pintype "passive"))
    )
    (net (code "90") (name "unconnected-(X1-R1_6-Pad5)") (class "Default")
      (node (ref "X1") (pin "5") (pinfunction "R1_6_5") (pintype "passive"))
    )
    (net (code "91") (name "unconnected-(X1-R1_7-Pad6)") (class "Default")
      (node (ref "X1") (pin "6") (pinfunction "R1_7_6") (pintype "passive"))
    )
    (net (code "92") (name "unconnected-(X1-R2_5-Pad1)") (class "Default")
      (node (ref "X1") (pin "1") (pinfunction "R2_5_1") (pintype "passive"))
    )
    (net (code "93") (name "unconnected-(X1-R2_6-Pad2)") (class "Default")
      (node (ref "X1") (pin "2") (pinfunction "R2_6_2") (pintype "passive"))
    )
    (net (code "94") (name "unconnected-(X1-R2_7-Pad3)") (class "Default")
      (node (ref "X1") (pin "3") (pinfunction "R2_7_3") (pintype "passive"))
    )
    (net (code "95") (name "unconnected-(X2-R1_5-Pad4)") (class "Default")
      (node (ref "X2") (pin "4") (pinfunction "R1_5_4") (pintype "passive"))
    )
    (net (code "96") (name "unconnected-(X2-R1_6-Pad5)") (class "Default")
      (node (ref "X2") (pin "5") (pinfunction "R1_6_5") (pintype "passive"))
    )
    (net (code "97") (name "unconnected-(X2-R1_7-Pad6)") (class "Default")
      (node (ref "X2") (pin "6") (pinfunction "R1_7_6") (pintype "passive"))
    )
    (net (code "98") (name "unconnected-(X2-R2_5-Pad1)") (class "Default")
      (node (ref "X2") (pin "1") (pinfunction "R2_5_1") (pintype "passive"))
    )
    (net (code "99") (name "unconnected-(X2-R2_6-Pad2)") (class "Default")
      (node (ref "X2") (pin "2") (pinfunction "R2_6_2") (pintype "passive"))
    )
    (net (code "100") (name "unconnected-(X2-R2_7-Pad3)") (class "Default")
      (node (ref "X2") (pin "3") (pinfunction "R2_7_3") (pintype "passive"))
    )
    (net (code "101") (name "unconnected-(X3-R1_5-Pad4)") (class "Default")
      (node (ref "X3") (pin "4") (pinfunction "R1_5_4") (pintype "passive"))
    )
    (net (code "102") (name "unconnected-(X3-R1_6-Pad5)") (class "Default")
      (node (ref "X3") (pin "5") (pinfunction "R1_6_5") (pintype "passive"))
    )
    (net (code "103") (name "unconnected-(X3-R1_7-Pad6)") (class "Default")
      (node (ref "X3") (pin "6") (pinfunction "R1_7_6") (pintype "passive"))
    )
    (net (code "104") (name "unconnected-(X3-R2_5-Pad1)") (class "Default")
      (node (ref "X3") (pin "1") (pinfunction "R2_5_1") (pintype "passive"))
    )
    (net (code "105") (name "unconnected-(X3-R2_6-Pad2)") (class "Default")
      (node (ref "X3") (pin "2") (pinfunction "R2_6_2") (pintype "passive"))
    )
    (net (code "106") (name "unconnected-(X3-R2_7-Pad3)") (class "Default")
      (node (ref "X3") (pin "3") (pinfunction "R2_7_3") (pintype "passive"))
    )
    (net (code "107") (name "unconnected-(X4-R1_5-Pad4)") (class "Default")
      (node (ref "X4") (pin "4") (pinfunction "R1_5_4") (pintype "passive"))
    )
    (net (code "108") (name "unconnected-(X4-R1_6-Pad5)") (class "Default")
      (node (ref "X4") (pin "5") (pinfunction "R1_6_5") (pintype "passive"))
    )
    (net (code "109") (name "unconnected-(X4-R1_7-Pad6)") (class "Default")
      (node (ref "X4") (pin "6") (pinfunction "R1_7_6") (pintype "passive"))
    )
    (net (code "110") (name "unconnected-(X4-R2_5-Pad1)") (class "Default")
      (node (ref "X4") (pin "1") (pinfunction "R2_5_1") (pintype "passive"))
    )
    (net (code "111") (name "unconnected-(X4-R2_6-Pad2)") (class "Default")
      (node (ref "X4") (pin "2") (pinfunction "R2_6_2") (pintype "passive"))
    )
    (net (code "112") (name "unconnected-(X4-R2_7-Pad3)") (class "Default")
      (node (ref "X4") (pin "3") (pinfunction "R2_7_3") (pintype "passive"))
    )
    (net (code "113") (name "unconnected-(X5-R1_5-Pad4)") (class "Default")
      (node (ref "X5") (pin "4") (pinfunction "R1_5_4") (pintype "passive"))
    )
    (net (code "114") (name "unconnected-(X5-R1_6-Pad5)") (class "Default")
      (node (ref "X5") (pin "5") (pinfunction "R1_6_5") (pintype "passive"))
    )
    (net (code "115") (name "unconnected-(X5-R1_7-Pad6)") (class "Default")
      (node (ref "X5") (pin "6") (pinfunction "R1_7_6") (pintype "passive"))
    )
    (net (code "116") (name "unconnected-(X5-R2_5-Pad1)") (class "Default")
      (node (ref "X5") (pin "1") (pinfunction "R2_5_1") (pintype "passive"))
    )
    (net (code "117") (name "unconnected-(X5-R2_6-Pad2)") (class "Default")
      (node (ref "X5") (pin "2") (pinfunction "R2_6_2") (pintype "passive"))
    )
    (net (code "118") (name "unconnected-(X5-R2_7-Pad3)") (class "Default")
      (node (ref "X5") (pin "3") (pinfunction "R2_7_3") (pintype "passive"))
    )
    (net (code "119") (name "unconnected-(X6-R1_5-Pad4)") (class "Default")
      (node (ref "X6") (pin "4") (pinfunction "R1_5_4") (pintype "passive"))
    )
    (net (code "120") (name "unconnected-(X6-R1_6-Pad5)") (class "Default")
      (node (ref "X6") (pin "5") (pinfunction "R1_6_5") (pintype "passive"))
    )
    (net (code "121") (name "unconnected-(X6-R1_7-Pad6)") (class "Default")
      (node (ref "X6") (pin "6") (pinfunction "R1_7_6") (pintype "passive"))
    )
    (net (code "122") (name "unconnected-(X6-R2_5-Pad1)") (class "Default")
      (node (ref "X6") (pin "1") (pinfunction "R2_5_1") (pintype "passive"))
    )
    (net (code "123") (name "unconnected-(X6-R2_6-Pad2)") (class "Default")
      (node (ref "X6") (pin "2") (pinfunction "R2_6_2") (pintype "passive"))
    )
    (net (code "124") (name "unconnected-(X6-R2_7-Pad3)") (class "Default")
      (node (ref "X6") (pin "3") (pinfunction "R2_7_3") (pintype "passive"))
    )
    (net (code "125") (name "unconnected-(X7-R1_5-Pad4)") (class "Default")
      (node (ref "X7") (pin "4") (pinfunction "R1_5_4") (pintype "passive"))
    )
    (net (code "126") (name "unconnected-(X7-R1_6-Pad5)") (class "Default")
      (node (ref "X7") (pin "5") (pinfunction "R1_6_5") (pintype "passive"))
    )
    (net (code "127") (name "unconnected-(X7-R1_7-Pad6)") (class "Default")
      (node (ref "X7") (pin "6") (pinfunction "R1_7_6") (pintype "passive"))
    )
    (net (code "128") (name "unconnected-(X7-R2_5-Pad1)") (class "Default")
      (node (ref "X7") (pin "1") (pinfunction "R2_5_1") (pintype "passive"))
    )
    (net (code "129") (name "unconnected-(X7-R2_6-Pad2)") (class "Default")
      (node (ref "X7") (pin "2") (pinfunction "R2_6_2") (pintype "passive"))
    )
    (net (code "130") (name "unconnected-(X7-R2_7-Pad3)") (class "Default")
      (node (ref "X7") (pin "3") (pinfunction "R2_7_3") (pintype "passive"))
    )
    (net (code "131") (name "unconnected-(X8-R2_5-Pad1)") (class "Default")
      (node (ref "X8") (pin "1") (pinfunction "R2_5_1") (pintype "passive"))
    )
    (net (code "132") (name "unconnected-(X8-R2_6-Pad2)") (class "Default")
      (node (ref "X8") (pin "2") (pinfunction "R2_6_2") (pintype "passive"))
    )
    (net (code "133") (name "unconnected-(X8-R2_7-Pad3)") (class "Default")
      (node (ref "X8") (pin "3") (pinfunction "R2_7_3") (pintype "passive"))
    )
    (net (code "134") (name "unconnected-(X9-+V-Pad3)") (class "Default")
      (node (ref "X9") (pin "3") (pinfunction "+V_3") (pintype "passive"))
    )
    (net (code "135") (name "unconnected-(X9--V-Pad4)") (class "Default")
      (node (ref "X9") (pin "4") (pinfunction "-V_4") (pintype "passive"))
    )
  )
)
